# LoadMix.net
KiCad netlist of a schematic drawn in Altium Designer
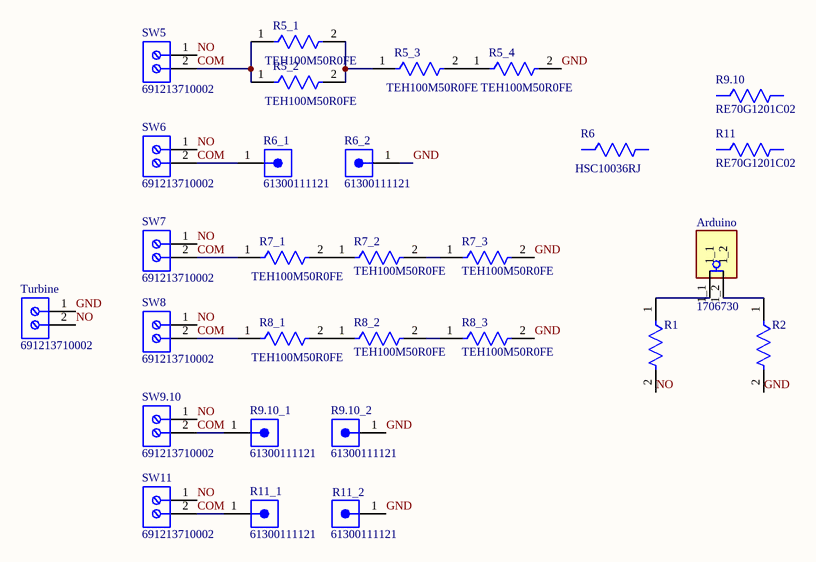
[diagram p0: LoadMix.SchDoc]

(export (version "E")
  (design (tool "Eeschema 10.0.6"))
  (components
    (comp (ref "Arduino")
      (value "1706730")
      (footprint "PHOENIX_1706730")
      (fields (field (name "MF") "{'manufacturer': u'Phoenix Contact'}"))
      (libsource (lib "Capstone") (part "1706730"))
    )
    (comp (ref "R1")
      (value "~")
      (footprint "FP-MRS25-MFG")
      (fields (field (name "TOLERANCE") "1%"))
      (libsource (lib "Altium Content Vault") (part "1029c3af85768c4190bb7ad29bc67b5"))
    )
    (comp (ref "R2")
      (value "~")
      (footprint "FP-MRS25-MFG")
      (fields (field (name "TOLERANCE") "1%"))
      (libsource (lib "Altium Content Vault") (part "1029c3af85768c4190bb7ad29bc67b5"))
    )
    (comp (ref "R5_1")
      (value "TEH100M50R0FE")
      (footprint "FP-TEH100-MFG")
      (description "TEH100M50R0FE Resistor, Thick Film, Res 50 Ohms, Pwr-Rtg100 W, Tol 1%, Radial, TO-247")
      (fields (field (name "TOLERANCE") "1%"))
      (libsource (lib "Altium Content Vault") (part "1029c3af85768c4190bb7ad29bc67b5"))
    )
    (comp (ref "R5_2")
      (value "TEH100M50R0FE")
      (footprint "FP-TEH100-MFG")
      (description "TEH100M50R0FE Resistor, Thick Film, Res 50 Ohms, Pwr-Rtg100 W, Tol 1%, Radial, TO-247")
      (fields (field (name "TOLERANCE") "1%"))
      (libsource (lib "Altium Content Vault") (part "1029c3af85768c4190bb7ad29bc67b5"))
    )
    (comp (ref "R5_3")
      (value "TEH100M50R0FE")
      (footprint "FP-TEH100-MFG")
      (description "TEH100M50R0FE Resistor, Thick Film, Res 50 Ohms, Pwr-Rtg100 W, Tol 1%, Radial, TO-247")
      (fields (field (name "TOLERANCE") "1%"))
      (libsource (lib "Altium Content Vault") (part "1029c3af85768c4190bb7ad29bc67b5"))
    )
    (comp (ref "R5_4")
      (value "TEH100M50R0FE")
      (footprint "FP-TEH100-MFG")
      (description "TEH100M50R0FE Resistor, Thick Film, Res 50 Ohms, Pwr-Rtg100 W, Tol 1%, Radial, TO-247")
      (fields (field (name "TOLERANCE") "1%"))
      (libsource (lib "Altium Content Vault") (part "1029c3af85768c4190bb7ad29bc67b5"))
    )
    (comp (ref "R6")
      (value "HSC10036RJ")
      (footprint "FP-HSC10036RJ-MFG")
      (description "RES CHAS MNT 36 OHM 5% 100W")
      (fields (field (name "TOLERANCE") "5%"))
      (libsource (lib "Altium Content Vault") (part "43bff7c1e99d1a2852b681fd378839c"))
    )
    (comp (ref "R6_1")
      (value "61300111121")
      (footprint "61300111121")
      (libsource (lib "Altium Content Vault") (part "Header_Male_1R_01P"))
    )
    (comp (ref "R6_2")
      (value "61300111121")
      (footprint "61300111121")
      (libsource (lib "Altium Content Vault") (part "Header_Male_1R_01P"))
    )
    (comp (ref "R7_1")
      (value "TEH100M50R0FE")
      (footprint "FP-TEH100-MFG")
      (description "TEH100M50R0FE Resistor, Thick Film, Res 50 Ohms, Pwr-Rtg100 W, Tol 1%, Radial, TO-247")
      (fields (field (name "TOLERANCE") "1%"))
      (libsource (lib "Altium Content Vault") (part "1029c3af85768c4190bb7ad29bc67b5"))
    )
    (comp (ref "R7_2")
      (value "TEH100M50R0FE")
      (footprint "FP-TEH100-MFG")
      (description "TEH100M50R0FE Resistor, Thick Film, Res 50 Ohms, Pwr-Rtg100 W, Tol 1%, Radial, TO-247")
      (fields (field (name "TOLERANCE") "1%"))
      (libsource (lib "Altium Content Vault") (part "1029c3af85768c4190bb7ad29bc67b5"))
    )
    (comp (ref "R7_3")
      (value "TEH100M50R0FE")
      (footprint "FP-TEH100-MFG")
      (description "TEH100M50R0FE Resistor, Thick Film, Res 50 Ohms, Pwr-Rtg100 W, Tol 1%, Radial, TO-247")
      (fields (field (name "TOLERANCE") "1%"))
      (libsource (lib "Altium Content Vault") (part "1029c3af85768c4190bb7ad29bc67b5"))
    )
    (comp (ref "R8_1")
      (value "TEH100M50R0FE")
      (footprint "FP-TEH100-MFG")
      (description "TEH100M50R0FE Resistor, Thick Film, Res 50 Ohms, Pwr-Rtg100 W, Tol 1%, Radial, TO-247")
      (fields (field (name "TOLERANCE") "1%"))
      (libsource (lib "Altium Content Vault") (part "1029c3af85768c4190bb7ad29bc67b5"))
    )
    (comp (ref "R8_2")
      (value "TEH100M50R0FE")
      (footprint "FP-TEH100-MFG")
      (description "TEH100M50R0FE Resistor, Thick Film, Res 50 Ohms, Pwr-Rtg100 W, Tol 1%, Radial, TO-247")
      (fields (field (name "TOLERANCE") "1%"))
      (libsource (lib "Altium Content Vault") (part "1029c3af85768c4190bb7ad29bc67b5"))
    )
    (comp (ref "R8_3")
      (value "TEH100M50R0FE")
      (footprint "FP-TEH100-MFG")
      (description "TEH100M50R0FE Resistor, Thick Film, Res 50 Ohms, Pwr-Rtg100 W, Tol 1%, Radial, TO-247")
      (fields (field (name "TOLERANCE") "1%"))
      (libsource (lib "Altium Content Vault") (part "1029c3af85768c4190bb7ad29bc67b5"))
    )
    (comp (ref "R9.10")
      (value "RE70G1201C02")
      (footprint "FP-RE70G-MFG")
      (description "RE70G1201C02 Res Wirewound 1.2K Ohm 1% 20W ±20ppm/C Aluminum Housed AXL Flange Mount Card")
      (fields (field (name "TOLERANCE") "1%"))
      (libsource (lib "Altium Content Vault") (part "43bff7c1e99d1a2852b681fd378839c"))
    )
    (comp (ref "R9.10_1")
      (value "61300111121")
      (footprint "61300111121")
      (libsource (lib "Altium Content Vault") (part "Header_Male_1R_01P"))
    )
    (comp (ref "R9.10_2")
      (value "61300111121")
      (footprint "61300111121")
      (libsource (lib "Altium Content Vault") (part "Header_Male_1R_01P"))
    )
    (comp (ref "R11")
      (value "RE70G1201C02")
      (footprint "FP-RE70G-MFG")
      (description "RE70G1201C02 Res Wirewound 1.2K Ohm 1% 20W ±20ppm/C Aluminum Housed AXL Flange Mount Card")
      (fields (field (name "TOLERANCE") "1%"))
      (libsource (lib "Altium Content Vault") (part "43bff7c1e99d1a2852b681fd378839c"))
    )
    (comp (ref "R11_1")
      (value "61300111121")
      (footprint "61300111121")
      (libsource (lib "Altium Content Vault") (part "Header_Male_1R_01P"))
    )
    (comp (ref "R11_2")
      (value "61300111121")
      (footprint "61300111121")
      (libsource (lib "Altium Content Vault") (part "Header_Male_1R_01P"))
    )
    (comp (ref "SW5")
      (value "691213710002")
      (footprint "691213710002")
      (fields (field (name "VOLTAGE") "300V"))
      (libsource (lib "Altium Content Vault") (part "TBL - 1R - 02P - Screw"))
    )
    (comp (ref "SW6")
      (value "691213710002")
      (footprint "691213710002")
      (fields (field (name "VOLTAGE") "300V"))
      (libsource (lib "Altium Content Vault") (part "TBL - 1R - 02P - Screw"))
    )
    (comp (ref "SW7")
      (value "691213710002")
      (footprint "691213710002")
      (fields (field (name "VOLTAGE") "300V"))
      (libsource (lib "Altium Content Vault") (part "TBL - 1R - 02P - Screw"))
    )
    (comp (ref "SW8")
      (value "691213710002")
      (footprint "691213710002")
      (fields (field (name "VOLTAGE") "300V"))
      (libsource (lib "Altium Content Vault") (part "TBL - 1R - 02P - Screw"))
    )
    (comp (ref "SW9.10")
      (value "691213710002")
      (footprint "691213710002")
      (fields (field (name "VOLTAGE") "300V"))
      (libsource (lib "Altium Content Vault") (part "TBL - 1R - 02P - Screw"))
    )
    (comp (ref "SW11")
      (value "691213710002")
      (footprint "691213710002")
      (fields (field (name "VOLTAGE") "300V"))
      (libsource (lib "Altium Content Vault") (part "TBL - 1R - 02P - Screw"))
    )
    (comp (ref "Turbine")
      (value "691213710002")
      (footprint "691213710002")
      (fields (field (name "VOLTAGE") "300V"))
      (libsource (lib "Altium Content Vault") (part "TBL - 1R - 02P - Screw"))
    )
  )
  (nets
    (net (code "1") (name "/COM") (class "Default")
      (node (ref "R11_1") (pin "1") (pinfunction "1_1") (pintype "passive"))
      (node (ref "R5_1") (pin "1") (pinfunction "1_1") (pintype "passive"))
      (node (ref "R5_2") (pin "1") (pinfunction "1_1") (pintype "passive"))
      (node (ref "R6_1") (pin "1") (pinfunction "1_1") (pintype "passive"))
      (node (ref "R7_1") (pin "1") (pinfunction "1_1") (pintype "passive"))
      (node (ref "R8_1") (pin "1") (pinfunction "1_1") (pintype "passive"))
      (node (ref "R9.10_1") (pin "1") (pinfunction "1_1") (pintype "passive"))
      (node (ref "SW11") (pin "2") (pinfunction "2_2") (pintype "passive"))
      (node (ref "SW5") (pin "2") (pinfunction "2_2") (pintype "passive"))
      (node (ref "SW6") (pin "2") (pinfunction "2_2") (pintype "passive"))
      (node (ref "SW7") (pin "2") (pinfunction "2_2") (pintype "passive"))
      (node (ref "SW8") (pin "2") (pinfunction "2_2") (pintype "passive"))
      (node (ref "SW9.10") (pin "2") (pinfunction "2_2") (pintype "passive"))
    )
    (net (code "2") (name "/GND") (class "Default")
      (node (ref "R11_2") (pin "1") (pinfunction "1_1") (pintype "passive"))
      (node (ref "R2") (pin "2") (pinfunction "2_2") (pintype "passive"))
      (node (ref "R5_4") (pin "2") (pinfunction "2_2") (pintype "passive"))
      (node (ref "R6_2") (pin "1") (pinfunction "1_1") (pintype "passive"))
      (node (ref "R7_3") (pin "2") (pinfunction "2_2") (pintype "passive"))
      (node (ref "R8_3") (pin "2") (pinfunction "2_2") (pintype "passive"))
      (node (ref "R9.10_2") (pin "1") (pinfunction "1_1") (pintype "passive"))
      (node (ref "Turbine") (pin "1") (pinfunction "1_1") (pintype "passive"))
    )
    (net (code "3") (name "/NO") (class "Default")
      (node (ref "R1") (pin "2") (pinfunction "2_2") (pintype "passive"))
      (node (ref "SW11") (pin "1") (pinfunction "1_1") (pintype "passive"))
      (node (ref "SW5") (pin "1") (pinfunction "1_1") (pintype "passive"))
      (node (ref "SW6") (pin "1") (pinfunction "1_1") (pintype "passive"))
      (node (ref "SW7") (pin "1") (pinfunction "1_1") (pintype "passive"))
      (node (ref "SW8") (pin "1") (pinfunction "1_1") (pintype "passive"))
      (node (ref "SW9.10") (pin "1") (pinfunction "1_1") (pintype "passive"))
      (node (ref "Turbine") (pin "2") (pinfunction "2_2") (pintype "passive"))
    )
    (net (code "4") (name "Net-(Arduino-Pad1_1)") (class "Default")
      (node (ref "Arduino") (pin "1_1") (pinfunction "1_1_1_1") (pintype "passive"))
      (node (ref "R1") (pin "1") (pinfunction "1_1") (pintype "passive"))
    )
    (net (code "5") (name "Net-(Arduino-Pad1_2)") (class "Default")
      (node (ref "Arduino") (pin "1_2") (pinfunction "1_2_1_2") (pintype "passive"))
      (node (ref "R2") (pin "1") (pinfunction "1_1") (pintype "passive"))
    )
    (net (code "6") (name "Net-(R5_1-Pad2)") (class "Default")
      (node (ref "R5_1") (pin "2") (pinfunction "2_2") (pintype "passive"))
      (node (ref "R5_2") (pin "2") (pinfunction "2_2") (pintype "passive"))
      (node (ref "R5_3") (pin "1") (pinfunction "1_1") (pintype "passive"))
    )
    (net (code "7") (name "Net-(R5_3-Pad2)") (class "Default")
      (node (ref "R5_3") (pin "2") (pinfunction "2_2") (pintype "passive"))
      (node (ref "R5_4") (pin "1") (pinfunction "1_1") (pintype "passive"))
    )
    (net (code "8") (name "Net-(R7_1-Pad2)") (class "Default")
      (node (ref "R7_1") (pin "2") (pinfunction "2_2") (pintype "passive"))
      (node (ref "R7_2") (pin "1") (pinfunction "1_1") (pintype "passive"))
    )
    (net (code "9") (name "Net-(R7_2-Pad2)") (class "Default")
      (node (ref "R7_2") (pin "2") (pinfunction "2_2") (pintype "passive"))
      (node (ref "R7_3") (pin "1") (pinfunction "1_1") (pintype "passive"))
    )
    (net (code "10") (name "Net-(R8_1-Pad2)") (class "Default")
      (node (ref "R8_1") (pin "2") (pinfunction "2_2") (pintype "passive"))
      (node (ref "R8_2") (pin "1") (pinfunction "1_1") (pintype "passive"))
    )
    (net (code "11") (name "Net-(R8_2-Pad2)") (class "Default")
      (node (ref "R8_2") (pin "2") (pinfunction "2_2") (pintype "passive"))
      (node (ref "R8_3") (pin "1") (pinfunction "1_1") (pintype "passive"))
    )
  )
)
